# POWER.net
KiCad netlist of a schematic drawn in Altium Designer
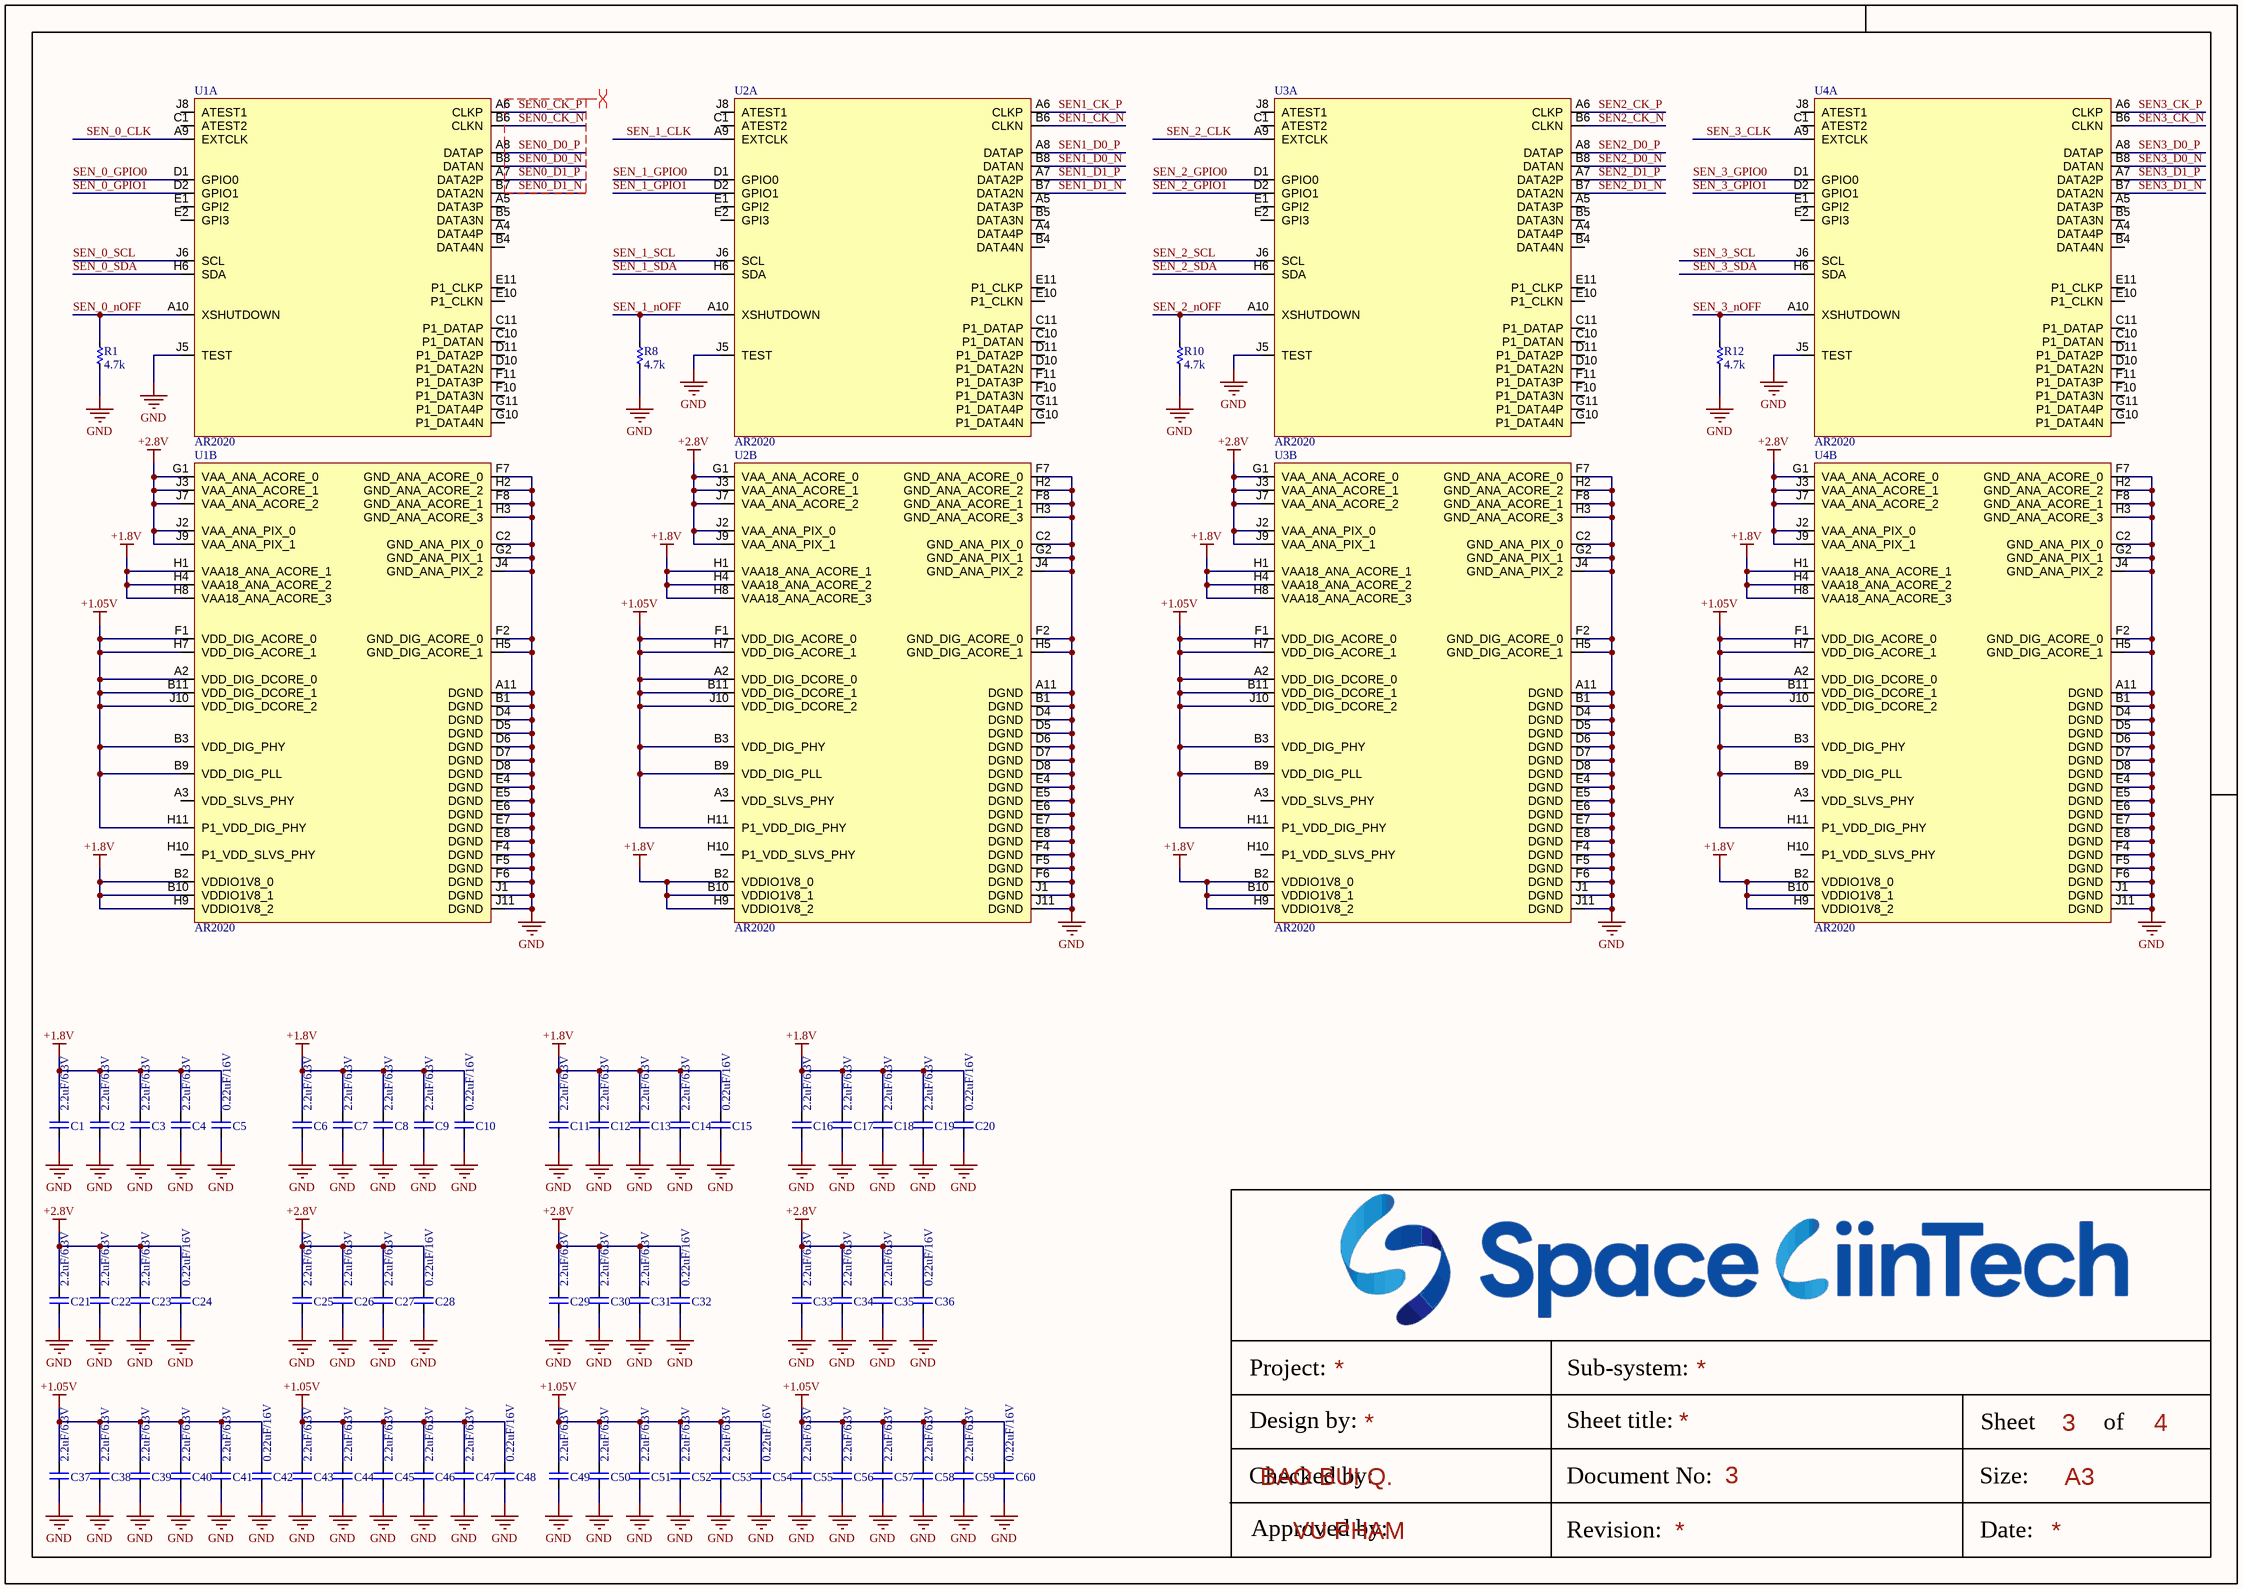
[diagram p0: POWER.SchDoc]

(export (version "E")
  (design (tool "Eeschema 10.0.6"))
  (components
    (comp (ref "C1")
      (value "2.2uF/6.3V")
      (footprint "CAP_C_1005X60")
      (description "CAP_Chip")
      (libsource (lib "LABLIB") (part "CAP_SMD"))
    )
    (comp (ref "C2")
      (value "2.2uF/6.3V")
      (footprint "CAP_C_1005X60")
      (description "CAP_Chip")
      (libsource (lib "LABLIB") (part "CAP_SMD"))
    )
    (comp (ref "C3")
      (value "2.2uF/6.3V")
      (footprint "CAP_C_1005X60")
      (description "CAP_Chip")
      (libsource (lib "LABLIB") (part "CAP_SMD"))
    )
    (comp (ref "C4")
      (value "2.2uF/6.3V")
      (footprint "CAP_C_1005X60")
      (description "CAP_Chip")
      (libsource (lib "LABLIB") (part "CAP_SMD"))
    )
    (comp (ref "C5")
      (value "0.22uF/16V")
      (footprint "CAP_C_1005X60")
      (description "CAP_Chip")
      (libsource (lib "LABLIB") (part "CAP_SMD"))
    )
    (comp (ref "C6")
      (value "2.2uF/6.3V")
      (footprint "CAP_C_1005X60")
      (description "CAP_Chip")
      (libsource (lib "LABLIB") (part "CAP_SMD"))
    )
    (comp (ref "C7")
      (value "2.2uF/6.3V")
      (footprint "CAP_C_1005X60")
      (description "CAP_Chip")
      (libsource (lib "LABLIB") (part "CAP_SMD"))
    )
    (comp (ref "C8")
      (value "2.2uF/6.3V")
      (footprint "CAP_C_1005X60")
      (description "CAP_Chip")
      (libsource (lib "LABLIB") (part "CAP_SMD"))
    )
    (comp (ref "C9")
      (value "2.2uF/6.3V")
      (footprint "CAP_C_1005X60")
      (description "CAP_Chip")
      (libsource (lib "LABLIB") (part "CAP_SMD"))
    )
    (comp (ref "C10")
      (value "0.22uF/16V")
      (footprint "CAP_C_1005X60")
      (description "CAP_Chip")
      (libsource (lib "LABLIB") (part "CAP_SMD"))
    )
    (comp (ref "C11")
      (value "2.2uF/6.3V")
      (footprint "CAP_C_1005X60")
      (description "CAP_Chip")
      (libsource (lib "LABLIB") (part "CAP_SMD"))
    )
    (comp (ref "C12")
      (value "2.2uF/6.3V")
      (footprint "CAP_C_1005X60")
      (description "CAP_Chip")
      (libsource (lib "LABLIB") (part "CAP_SMD"))
    )
    (comp (ref "C13")
      (value "2.2uF/6.3V")
      (footprint "CAP_C_1005X60")
      (description "CAP_Chip")
      (libsource (lib "LABLIB") (part "CAP_SMD"))
    )
    (comp (ref "C14")
      (value "2.2uF/6.3V")
      (footprint "CAP_C_1005X60")
      (description "CAP_Chip")
      (libsource (lib "LABLIB") (part "CAP_SMD"))
    )
    (comp (ref "C15")
      (value "0.22uF/16V")
      (footprint "CAP_C_1005X60")
      (description "CAP_Chip")
      (libsource (lib "LABLIB") (part "CAP_SMD"))
    )
    (comp (ref "C16")
      (value "2.2uF/6.3V")
      (footprint "CAP_C_1005X60")
      (description "CAP_Chip")
      (libsource (lib "LABLIB") (part "CAP_SMD"))
    )
    (comp (ref "C17")
      (value "2.2uF/6.3V")
      (footprint "CAP_C_1005X60")
      (description "CAP_Chip")
      (libsource (lib "LABLIB") (part "CAP_SMD"))
    )
    (comp (ref "C18")
      (value "2.2uF/6.3V")
      (footprint "CAP_C_1005X60")
      (description "CAP_Chip")
      (libsource (lib "LABLIB") (part "CAP_SMD"))
    )
    (comp (ref "C19")
      (value "2.2uF/6.3V")
      (footprint "CAP_C_1005X60")
      (description "CAP_Chip")
      (libsource (lib "LABLIB") (part "CAP_SMD"))
    )
    (comp (ref "C20")
      (value "0.22uF/16V")
      (footprint "CAP_C_1005X60")
      (description "CAP_Chip")
      (libsource (lib "LABLIB") (part "CAP_SMD"))
    )
    (comp (ref "C21")
      (value "2.2uF/6.3V")
      (footprint "CAP_C_1005X60")
      (description "CAP_Chip")
      (libsource (lib "LABLIB") (part "CAP_SMD"))
    )
    (comp (ref "C22")
      (value "2.2uF/6.3V")
      (footprint "CAP_C_1005X60")
      (description "CAP_Chip")
      (libsource (lib "LABLIB") (part "CAP_SMD"))
    )
    (comp (ref "C23")
      (value "2.2uF/6.3V")
      (footprint "CAP_C_1005X60")
      (description "CAP_Chip")
      (libsource (lib "LABLIB") (part "CAP_SMD"))
    )
    (comp (ref "C24")
      (value "0.22uF/16V")
      (footprint "CAP_C_1005X60")
      (description "CAP_Chip")
      (libsource (lib "LABLIB") (part "CAP_SMD"))
    )
    (comp (ref "C25")
      (value "2.2uF/6.3V")
      (footprint "CAP_C_1005X60")
      (description "CAP_Chip")
      (libsource (lib "LABLIB") (part "CAP_SMD"))
    )
    (comp (ref "C26")
      (value "2.2uF/6.3V")
      (footprint "CAP_C_1005X60")
      (description "CAP_Chip")
      (libsource (lib "LABLIB") (part "CAP_SMD"))
    )
    (comp (ref "C27")
      (value "2.2uF/6.3V")
      (footprint "CAP_C_1005X60")
      (description "CAP_Chip")
      (libsource (lib "LABLIB") (part "CAP_SMD"))
    )
    (comp (ref "C28")
      (value "0.22uF/16V")
      (footprint "CAP_C_1005X60")
      (description "CAP_Chip")
      (libsource (lib "LABLIB") (part "CAP_SMD"))
    )
    (comp (ref "C29")
      (value "2.2uF/6.3V")
      (footprint "CAP_C_1005X60")
      (description "CAP_Chip")
      (libsource (lib "LABLIB") (part "CAP_SMD"))
    )
    (comp (ref "C30")
      (value "2.2uF/6.3V")
      (footprint "CAP_C_1005X60")
      (description "CAP_Chip")
      (libsource (lib "LABLIB") (part "CAP_SMD"))
    )
    (comp (ref "C31")
      (value "2.2uF/6.3V")
      (footprint "CAP_C_1005X60")
      (description "CAP_Chip")
      (libsource (lib "LABLIB") (part "CAP_SMD"))
    )
    (comp (ref "C32")
      (value "0.22uF/16V")
      (footprint "CAP_C_1005X60")
      (description "CAP_Chip")
      (libsource (lib "LABLIB") (part "CAP_SMD"))
    )
    (comp (ref "C33")
      (value "2.2uF/6.3V")
      (footprint "CAP_C_1005X60")
      (description "CAP_Chip")
      (libsource (lib "LABLIB") (part "CAP_SMD"))
    )
    (comp (ref "C34")
      (value "2.2uF/6.3V")
      (footprint "CAP_C_1005X60")
      (description "CAP_Chip")
      (libsource (lib "LABLIB") (part "CAP_SMD"))
    )
    (comp (ref "C35")
      (value "2.2uF/6.3V")
      (footprint "CAP_C_1005X60")
      (description "CAP_Chip")
      (libsource (lib "LABLIB") (part "CAP_SMD"))
    )
    (comp (ref "C36")
      (value "0.22uF/16V")
      (footprint "CAP_C_1005X60")
      (description "CAP_Chip")
      (libsource (lib "LABLIB") (part "CAP_SMD"))
    )
    (comp (ref "C37")
      (value "2.2uF/6.3V")
      (footprint "CAP_C_1005X60")
      (description "CAP_Chip")
      (libsource (lib "LABLIB") (part "CAP_SMD"))
    )
    (comp (ref "C38")
      (value "2.2uF/6.3V")
      (footprint "CAP_C_1005X60")
      (description "CAP_Chip")
      (libsource (lib "LABLIB") (part "CAP_SMD"))
    )
    (comp (ref "C39")
      (value "2.2uF/6.3V")
      (footprint "CAP_C_1005X60")
      (description "CAP_Chip")
      (libsource (lib "LABLIB") (part "CAP_SMD"))
    )
    (comp (ref "C40")
      (value "2.2uF/6.3V")
      (footprint "CAP_C_1005X60")
      (description "CAP_Chip")
      (libsource (lib "LABLIB") (part "CAP_SMD"))
    )
    (comp (ref "C41")
      (value "2.2uF/6.3V")
      (footprint "CAP_C_1005X60")
      (description "CAP_Chip")
      (libsource (lib "LABLIB") (part "CAP_SMD"))
    )
    (comp (ref "C42")
      (value "0.22uF/16V")
      (footprint "CAP_C_1005X60")
      (description "CAP_Chip")
      (libsource (lib "LABLIB") (part "CAP_SMD"))
    )
    (comp (ref "C43")
      (value "2.2uF/6.3V")
      (footprint "CAP_C_1005X60")
      (description "CAP_Chip")
      (libsource (lib "LABLIB") (part "CAP_SMD"))
    )
    (comp (ref "C44")
      (value "2.2uF/6.3V")
      (footprint "CAP_C_1005X60")
      (description "CAP_Chip")
      (libsource (lib "LABLIB") (part "CAP_SMD"))
    )
    (comp (ref "C45")
      (value "2.2uF/6.3V")
      (footprint "CAP_C_1005X60")
      (description "CAP_Chip")
      (libsource (lib "LABLIB") (part "CAP_SMD"))
    )
    (comp (ref "C46")
      (value "2.2uF/6.3V")
      (footprint "CAP_C_1005X60")
      (description "CAP_Chip")
      (libsource (lib "LABLIB") (part "CAP_SMD"))
    )
    (comp (ref "C47")
      (value "2.2uF/6.3V")
      (footprint "CAP_C_1005X60")
      (description "CAP_Chip")
      (libsource (lib "LABLIB") (part "CAP_SMD"))
    )
    (comp (ref "C48")
      (value "0.22uF/16V")
      (footprint "CAP_C_1005X60")
      (description "CAP_Chip")
      (libsource (lib "LABLIB") (part "CAP_SMD"))
    )
    (comp (ref "C49")
      (value "2.2uF/6.3V")
      (footprint "CAP_C_1005X60")
      (description "CAP_Chip")
      (libsource (lib "LABLIB") (part "CAP_SMD"))
    )
    (comp (ref "C50")
      (value "2.2uF/6.3V")
      (footprint "CAP_C_1005X60")
      (description "CAP_Chip")
      (libsource (lib "LABLIB") (part "CAP_SMD"))
    )
    (comp (ref "C51")
      (value "2.2uF/6.3V")
      (footprint "CAP_C_1005X60")
      (description "CAP_Chip")
      (libsource (lib "LABLIB") (part "CAP_SMD"))
    )
    (comp (ref "C52")
      (value "2.2uF/6.3V")
      (footprint "CAP_C_1005X60")
      (description "CAP_Chip")
      (libsource (lib "LABLIB") (part "CAP_SMD"))
    )
    (comp (ref "C53")
      (value "2.2uF/6.3V")
      (footprint "CAP_C_1005X60")
      (description "CAP_Chip")
      (libsource (lib "LABLIB") (part "CAP_SMD"))
    )
    (comp (ref "C54")
      (value "0.22uF/16V")
      (footprint "CAP_C_1005X60")
      (description "CAP_Chip")
      (libsource (lib "LABLIB") (part "CAP_SMD"))
    )
    (comp (ref "C55")
      (value "2.2uF/6.3V")
      (footprint "CAP_C_1005X60")
      (description "CAP_Chip")
      (libsource (lib "LABLIB") (part "CAP_SMD"))
    )
    (comp (ref "C56")
      (value "2.2uF/6.3V")
      (footprint "CAP_C_1005X60")
      (description "CAP_Chip")
      (libsource (lib "LABLIB") (part "CAP_SMD"))
    )
    (comp (ref "C57")
      (value "2.2uF/6.3V")
      (footprint "CAP_C_1005X60")
      (description "CAP_Chip")
      (libsource (lib "LABLIB") (part "CAP_SMD"))
    )
    (comp (ref "C58")
      (value "2.2uF/6.3V")
      (footprint "CAP_C_1005X60")
      (description "CAP_Chip")
      (libsource (lib "LABLIB") (part "CAP_SMD"))
    )
    (comp (ref "C59")
      (value "2.2uF/6.3V")
      (footprint "CAP_C_1005X60")
      (description "CAP_Chip")
      (libsource (lib "LABLIB") (part "CAP_SMD"))
    )
    (comp (ref "C60")
      (value "0.22uF/16V")
      (footprint "CAP_C_1005X60")
      (description "CAP_Chip")
      (libsource (lib "LABLIB") (part "CAP_SMD"))
    )
    (comp (ref "R1")
      (value "4.7k")
      (footprint "RES_C_1005X40")
      (description "RES-Chip")
      (fields
        (field (name "MANUFACTURER") "Generic Components")
        (field (name "PUBLISHER") "Altium Hobart Technology Centre")
      )
      (libsource (lib "LABLIB") (part "RES-SMD"))
    )
    (comp (ref "R8")
      (value "4.7k")
      (footprint "RES_C_1005X40")
      (description "RES-Chip")
      (fields
        (field (name "MANUFACTURER") "Generic Components")
        (field (name "PUBLISHER") "Altium Hobart Technology Centre")
      )
      (libsource (lib "LABLIB") (part "RES-SMD"))
    )
    (comp (ref "R10")
      (value "4.7k")
      (footprint "RES_C_1005X40")
      (description "RES-Chip")
      (fields
        (field (name "MANUFACTURER") "Generic Components")
        (field (name "PUBLISHER") "Altium Hobart Technology Centre")
      )
      (libsource (lib "LABLIB") (part "RES-SMD"))
    )
    (comp (ref "R12")
      (value "4.7k")
      (footprint "RES_C_1005X40")
      (description "RES-Chip")
      (fields
        (field (name "MANUFACTURER") "Generic Components")
        (field (name "PUBLISHER") "Altium Hobart Technology Centre")
      )
      (libsource (lib "LABLIB") (part "RES-SMD"))
    )
    (comp (ref "U1")
      (value "AR2020")
      (footprint "BGA78C100P11X9_1300X1050X210")
      (libsource (lib "CAMERA_SchLib") (part "AR2020"))
    )
    (comp (ref "U2")
      (value "AR2020")
      (footprint "BGA78C100P11X9_1300X1050X210")
      (libsource (lib "CAMERA_SchLib") (part "AR2020"))
    )
    (comp (ref "U3")
      (value "AR2020")
      (footprint "BGA78C100P11X9_1300X1050X210")
      (libsource (lib "CAMERA_SchLib") (part "AR2020"))
    )
    (comp (ref "U4")
      (value "AR2020")
      (footprint "BGA78C100P11X9_1300X1050X210")
      (libsource (lib "CAMERA_SchLib") (part "AR2020"))
    )
  )
  (nets
    (net (code "1") (name "+1.05V") (class "Default")
      (node (ref "C37") (pin "2") (pinfunction "2_2") (pintype "passive"))
      (node (ref "C38") (pin "2") (pinfunction "2_2") (pintype "passive"))
      (node (ref "C39") (pin "2") (pinfunction "2_2") (pintype "passive"))
      (node (ref "C40") (pin "2") (pinfunction "2_2") (pintype "passive"))
      (node (ref "C41") (pin "2") (pinfunction "2_2") (pintype "passive"))
      (node (ref "C42") (pin "2") (pinfunction "2_2") (pintype "passive"))
      (node (ref "C43") (pin "2") (pinfunction "2_2") (pintype "passive"))
      (node (ref "C44") (pin "2") (pinfunction "2_2") (pintype "passive"))
      (node (ref "C45") (pin "2") (pinfunction "2_2") (pintype "passive"))
      (node (ref "C46") (pin "2") (pinfunction "2_2") (pintype "passive"))
      (node (ref "C47") (pin "2") (pinfunction "2_2") (pintype "passive"))
      (node (ref "C48") (pin "2") (pinfunction "2_2") (pintype "passive"))
      (node (ref "C49") (pin "2") (pinfunction "2_2") (pintype "passive"))
      (node (ref "C50") (pin "2") (pinfunction "2_2") (pintype "passive"))
      (node (ref "C51") (pin "2") (pinfunction "2_2") (pintype "passive"))
      (node (ref "C52") (pin "2") (pinfunction "2_2") (pintype "passive"))
      (node (ref "C53") (pin "2") (pinfunction "2_2") (pintype "passive"))
      (node (ref "C54") (pin "2") (pinfunction "2_2") (pintype "passive"))
      (node (ref "C55") (pin "2") (pinfunction "2_2") (pintype "passive"))
      (node (ref "C56") (pin "2") (pinfunction "2_2") (pintype "passive"))
      (node (ref "C57") (pin "2") (pinfunction "2_2") (pintype "passive"))
      (node (ref "C58") (pin "2") (pinfunction "2_2") (pintype "passive"))
      (node (ref "C59") (pin "2") (pinfunction "2_2") (pintype "passive"))
      (node (ref "C60") (pin "2") (pinfunction "2_2") (pintype "passive"))
      (node (ref "U1") (pin "A2") (pinfunction "VDD_DIG_DCORE_0_A2") (pintype "passive"))
      (node (ref "U1") (pin "B11") (pinfunction "VDD_DIG_DCORE_1_B11") (pintype "passive"))
      (node (ref "U1") (pin "B3") (pinfunction "VDD_DIG_PHY_B3") (pintype "passive"))
      (node (ref "U1") (pin "B9") (pinfunction "VDD_DIG_PLL_B9") (pintype "passive"))
      (node (ref "U1") (pin "F1") (pinfunction "VDD_DIG_ACORE_0_F1") (pintype "passive"))
      (node (ref "U1") (pin "H11") (pinfunction "P1_VDD_DIG_PHY_H11") (pintype "passive"))
      (node (ref "U1") (pin "H7") (pinfunction "VDD_DIG_ACORE_1_H7") (pintype "passive"))
      (node (ref "U1") (pin "J10") (pinfunction "VDD_DIG_DCORE_2_J10") (pintype "passive"))
      (node (ref "U2") (pin "A2") (pinfunction "VDD_DIG_DCORE_0_A2") (pintype "passive"))
      (node (ref "U2") (pin "B11") (pinfunction "VDD_DIG_DCORE_1_B11") (pintype "passive"))
      (node (ref "U2") (pin "B3") (pinfunction "VDD_DIG_PHY_B3") (pintype "passive"))
      (node (ref "U2") (pin "B9") (pinfunction "VDD_DIG_PLL_B9") (pintype "passive"))
      (node (ref "U2") (pin "F1") (pinfunction "VDD_DIG_ACORE_0_F1") (pintype "passive"))
      (node (ref "U2") (pin "H11") (pinfunction "P1_VDD_DIG_PHY_H11") (pintype "passive"))
      (node (ref "U2") (pin "H7") (pinfunction "VDD_DIG_ACORE_1_H7") (pintype "passive"))
      (node (ref "U2") (pin "J10") (pinfunction "VDD_DIG_DCORE_2_J10") (pintype "passive"))
      (node (ref "U3") (pin "A2") (pinfunction "VDD_DIG_DCORE_0_A2") (pintype "passive"))
      (node (ref "U3") (pin "B11") (pinfunction "VDD_DIG_DCORE_1_B11") (pintype "passive"))
      (node (ref "U3") (pin "B3") (pinfunction "VDD_DIG_PHY_B3") (pintype "passive"))
      (node (ref "U3") (pin "B9") (pinfunction "VDD_DIG_PLL_B9") (pintype "passive"))
      (node (ref "U3") (pin "F1") (pinfunction "VDD_DIG_ACORE_0_F1") (pintype "passive"))
      (node (ref "U3") (pin "H11") (pinfunction "P1_VDD_DIG_PHY_H11") (pintype "passive"))
      (node (ref "U3") (pin "H7") (pinfunction "VDD_DIG_ACORE_1_H7") (pintype "passive"))
      (node (ref "U3") (pin "J10") (pinfunction "VDD_DIG_DCORE_2_J10") (pintype "passive"))
      (node (ref "U4") (pin "A2") (pinfunction "VDD_DIG_DCORE_0_A2") (pintype "passive"))
      (node (ref "U4") (pin "B11") (pinfunction "VDD_DIG_DCORE_1_B11") (pintype "passive"))
      (node (ref "U4") (pin "B3") (pinfunction "VDD_DIG_PHY_B3") (pintype "passive"))
      (node (ref "U4") (pin "B9") (pinfunction "VDD_DIG_PLL_B9") (pintype "passive"))
      (node (ref "U4") (pin "F1") (pinfunction "VDD_DIG_ACORE_0_F1") (pintype "passive"))
      (node (ref "U4") (pin "H11") (pinfunction "P1_VDD_DIG_PHY_H11") (pintype "passive"))
      (node (ref "U4") (pin "H7") (pinfunction "VDD_DIG_ACORE_1_H7") (pintype "passive"))
      (node (ref "U4") (pin "J10") (pinfunction "VDD_DIG_DCORE_2_J10") (pintype "passive"))
    )
    (net (code "2") (name "+1.8V") (class "Default")
      (node (ref "C1") (pin "2") (pinfunction "2_2") (pintype "passive"))
      (node (ref "C10") (pin "2") (pinfunction "2_2") (pintype "passive"))
      (node (ref "C11") (pin "2") (pinfunction "2_2") (pintype "passive"))
      (node (ref "C12") (pin "2") (pinfunction "2_2") (pintype "passive"))
      (node (ref "C13") (pin "2") (pinfunction "2_2") (pintype "passive"))
      (node (ref "C14") (pin "2") (pinfunction "2_2") (pintype "passive"))
      (node (ref "C15") (pin "2") (pinfunction "2_2") (pintype "passive"))
      (node (ref "C16") (pin "2") (pinfunction "2_2") (pintype "passive"))
      (node (ref "C17") (pin "2") (pinfunction "2_2") (pintype "passive"))
      (node (ref "C18") (pin "2") (pinfunction "2_2") (pintype "passive"))
      (node (ref "C19") (pin "2") (pinfunction "2_2") (pintype "passive"))
      (node (ref "C2") (pin "2") (pinfunction "2_2") (pintype "passive"))
      (node (ref "C20") (pin "2") (pinfunction "2_2") (pintype "passive"))
      (node (ref "C3") (pin "2") (pinfunction "2_2") (pintype "passive"))
      (node (ref "C4") (pin "2") (pinfunction "2_2") (pintype "passive"))
      (node (ref "C5") (pin "2") (pinfunction "2_2") (pintype "passive"))
      (node (ref "C6") (pin "2") (pinfunction "2_2") (pintype "passive"))
      (node (ref "C7") (pin "2") (pinfunction "2_2") (pintype "passive"))
      (node (ref "C8") (pin "2") (pinfunction "2_2") (pintype "passive"))
      (node (ref "C9") (pin "2") (pinfunction "2_2") (pintype "passive"))
      (node (ref "U1") (pin "B10") (pinfunction "VDDIO1V8_1_B10") (pintype "passive"))
      (node (ref "U1") (pin "B2") (pinfunction "VDDIO1V8_0_B2") (pintype "passive"))
      (node (ref "U1") (pin "H1") (pinfunction "VAA18_ANA_ACORE_1_H1") (pintype "passive"))
      (node (ref "U1") (pin "H4") (pinfunction "VAA18_ANA_ACORE_2_H4") (pintype "passive"))
      (node (ref "U1") (pin "H8") (pinfunction "VAA18_ANA_ACORE_3_H8") (pintype "passive"))
      (node (ref "U1") (pin "H9") (pinfunction "VDDIO1V8_2_H9") (pintype "passive"))
      (node (ref "U2") (pin "B10") (pinfunction "VDDIO1V8_1_B10") (pintype "passive"))
      (node (ref "U2") (pin "B2") (pinfunction "VDDIO1V8_0_B2") (pintype "passive"))
      (node (ref "U2") (pin "H1") (pinfunction "VAA18_ANA_ACORE_1_H1") (pintype "passive"))
      (node (ref "U2") (pin "H4") (pinfunction "VAA18_ANA_ACORE_2_H4") (pintype "passive"))
      (node (ref "U2") (pin "H8") (pinfunction "VAA18_ANA_ACORE_3_H8") (pintype "passive"))
      (node (ref "U2") (pin "H9") (pinfunction "VDDIO1V8_2_H9") (pintype "passive"))
      (node (ref "U3") (pin "B10") (pinfunction "VDDIO1V8_1_B10") (pintype "passive"))
      (node (ref "U3") (pin "B2") (pinfunction "VDDIO1V8_0_B2") (pintype "passive"))
      (node (ref "U3") (pin "H1") (pinfunction "VAA18_ANA_ACORE_1_H1") (pintype "passive"))
      (node (ref "U3") (pin "H4") (pinfunction "VAA18_ANA_ACORE_2_H4") (pintype "passive"))
      (node (ref "U3") (pin "H8") (pinfunction "VAA18_ANA_ACORE_3_H8") (pintype "passive"))
      (node (ref "U3") (pin "H9") (pinfunction "VDDIO1V8_2_H9") (pintype "passive"))
      (node (ref "U4") (pin "B10") (pinfunction "VDDIO1V8_1_B10") (pintype "passive"))
      (node (ref "U4") (pin "B2") (pinfunction "VDDIO1V8_0_B2") (pintype "passive"))
      (node (ref "U4") (pin "H1") (pinfunction "VAA18_ANA_ACORE_1_H1") (pintype "passive"))
      (node (ref "U4") (pin "H4") (pinfunction "VAA18_ANA_ACORE_2_H4") (pintype "passive"))
      (node (ref "U4") (pin "H8") (pinfunction "VAA18_ANA_ACORE_3_H8") (pintype "passive"))
      (node (ref "U4") (pin "H9") (pinfunction "VDDIO1V8_2_H9") (pintype "passive"))
    )
    (net (code "3") (name "+2.8V") (class "Default")
      (node (ref "C21") (pin "2") (pinfunction "2_2") (pintype "passive"))
      (node (ref "C22") (pin "2") (pinfunction "2_2") (pintype "passive"))
      (node (ref "C23") (pin "2") (pinfunction "2_2") (pintype "passive"))
      (node (ref "C24") (pin "2") (pinfunction "2_2") (pintype "passive"))
      (node (ref "C25") (pin "2") (pinfunction "2_2") (pintype "passive"))
      (node (ref "C26") (pin "2") (pinfunction "2_2") (pintype "passive"))
      (node (ref "C27") (pin "2") (pinfunction "2_2") (pintype "passive"))
      (node (ref "C28") (pin "2") (pinfunction "2_2") (pintype "passive"))
      (node (ref "C29") (pin "2") (pinfunction "2_2") (pintype "passive"))
      (node (ref "C30") (pin "2") (pinfunction "2_2") (pintype "passive"))
      (node (ref "C31") (pin "2") (pinfunction "2_2") (pintype "passive"))
      (node (ref "C32") (pin "2") (pinfunction "2_2") (pintype "passive"))
      (node (ref "C33") (pin "2") (pinfunction "2_2") (pintype "passive"))
      (node (ref "C34") (pin "2") (pinfunction "2_2") (pintype "passive"))
      (node (ref "C35") (pin "2") (pinfunction "2_2") (pintype "passive"))
      (node (ref "C36") (pin "2") (pinfunction "2_2") (pintype "passive"))
      (node (ref "U1") (pin "G1") (pinfunction "VAA_ANA_ACORE_0_G1") (pintype "passive"))
      (node (ref "U1") (pin "J2") (pinfunction "VAA_ANA_PIX_0_J2") (pintype "passive"))
      (node (ref "U1") (pin "J3") (pinfunction "VAA_ANA_ACORE_1_J3") (pintype "passive"))
      (node (ref "U1") (pin "J7") (pinfunction "VAA_ANA_ACORE_2_J7") (pintype "passive"))
      (node (ref "U1") (pin "J9") (pinfunction "VAA_ANA_PIX_1_J9") (pintype "passive"))
      (node (ref "U2") (pin "G1") (pinfunction "VAA_ANA_ACORE_0_G1") (pintype "passive"))
      (node (ref "U2") (pin "J2") (pinfunction "VAA_ANA_PIX_0_J2") (pintype "passive"))
      (node (ref "U2") (pin "J3") (pinfunction "VAA_ANA_ACORE_1_J3") (pintype "passive"))
      (node (ref "U2") (pin "J7") (pinfunction "VAA_ANA_ACORE_2_J7") (pintype "passive"))
      (node (ref "U2") (pin "J9") (pinfunction "VAA_ANA_PIX_1_J9") (pintype "passive"))
      (node (ref "U3") (pin "G1") (pinfunction "VAA_ANA_ACORE_0_G1") (pintype "passive"))
      (node (ref "U3") (pin "J2") (pinfunction "VAA_ANA_PIX_0_J2") (pintype "passive"))
      (node (ref "U3") (pin "J3") (pinfunction "VAA_ANA_ACORE_1_J3") (pintype "passive"))
      (node (ref "U3") (pin "J7") (pinfunction "VAA_ANA_ACORE_2_J7") (pintype "passive"))
      (node (ref "U3") (pin "J9") (pinfunction "VAA_ANA_PIX_1_J9") (pintype "passive"))
      (node (ref "U4") (pin "G1") (pinfunction "VAA_ANA_ACORE_0_G1") (pintype "passive"))
      (node (ref "U4") (pin "J2") (pinfunction "VAA_ANA_PIX_0_J2") (pintype "passive"))
      (node (ref "U4") (pin "J3") (pinfunction "VAA_ANA_ACORE_1_J3") (pintype "passive"))
      (node (ref "U4") (pin "J7") (pinfunction "VAA_ANA_ACORE_2_J7") (pintype "passive"))
      (node (ref "U4") (pin "J9") (pinfunction "VAA_ANA_PIX_1_J9") (pintype "passive"))
    )
    (net (code "4") (name "/SEN0_CK_N") (class "Default")
      (node (ref "U1") (pin "B6") (pinfunction "CLKN_B6") (pintype "passive"))
    )
    (net (code "5") (name "/SEN0_CK_P") (class "Default")
      (node (ref "U1") (pin "A6") (pinfunction "CLKP_A6") (pintype "passive"))
    )
    (net (code "6") (name "/SEN0_D0_N") (class "Default")
      (node (ref "U1") (pin "B8") (pinfunction "DATAN_B8") (pintype "passive"))
    )
    (net (code "7") (name "/SEN0_D0_P") (class "Default")
      (node (ref "U1") (pin "A8") (pinfunction "DATAP_A8") (pintype "passive"))
    )
    (net (code "8") (name "/SEN0_D1_N") (class "Default")
      (node (ref "U1") (pin "B7") (pinfunction "DATA2N_B7") (pintype "passive"))
    )
    (net (code "9") (name "/SEN0_D1_P") (class "Default")
      (node (ref "U1") (pin "A7") (pinfunction "DATA2P_A7") (pintype "passive"))
    )
    (net (code "10") (name "/SEN1_CK_N") (class "Default")
      (node (ref "U2") (pin "B6") (pinfunction "CLKN_B6") (pintype "passive"))
    )
    (net (code "11") (name "/SEN1_CK_P") (class "Default")
      (node (ref "U2") (pin "A6") (pinfunction "CLKP_A6") (pintype "passive"))
    )
    (net (code "12") (name "/SEN1_D0_N") (class "Default")
      (node (ref "U2") (pin "B8") (pinfunction "DATAN_B8") (pintype "passive"))
    )
    (net (code "13") (name "/SEN1_D0_P") (class "Default")
      (node (ref "U2") (pin "A8") (pinfunction "DATAP_A8") (pintype "passive"))
    )
    (net (code "14") (name "/SEN1_D1_N") (class "Default")
      (node (ref "U2") (pin "B7") (pinfunction "DATA2N_B7") (pintype "passive"))
    )
    (net (code "15") (name "/SEN1_D1_P") (class "Default")
      (node (ref "U2") (pin "A7") (pinfunction "DATA2P_A7") (pintype "passive"))
    )
    (net (code "16") (name "/SEN2_CK_N") (class "Default")
      (node (ref "U3") (pin "B6") (pinfunction "CLKN_B6") (pintype "passive"))
    )
    (net (code "17") (name "/SEN2_CK_P") (class "Default")
      (node (ref "U3") (pin "A6") (pinfunction "CLKP_A6") (pintype "passive"))
    )
    (net (code "18") (name "/SEN2_D0_N") (class "Default")
      (node (ref "U3") (pin "B8") (pinfunction "DATAN_B8") (pintype "passive"))
    )
    (net (code "19") (name "/SEN2_D0_P") (class "Default")
      (node (ref "U3") (pin "A8") (pinfunction "DATAP_A8") (pintype "passive"))
    )
    (net (code "20") (name "/SEN2_D1_N") (class "Default")
      (node (ref "U3") (pin "B7") (pinfunction "DATA2N_B7") (pintype "passive"))
    )
    (net (code "21") (name "/SEN2_D1_P") (class "Default")
      (node (ref "U3") (pin "A7") (pinfunction "DATA2P_A7") (pintype "passive"))
    )
    (net (code "22") (name "/SEN3_CK_N") (class "Default")
      (node (ref "U4") (pin "B6") (pinfunction "CLKN_B6") (pintype "passive"))
    )
    (net (code "23") (name "/SEN3_CK_P") (class "Default")
      (node (ref "U4") (pin "A6") (pinfunction "CLKP_A6") (pintype "passive"))
    )
    (net (code "24") (name "/SEN3_D0_N") (class "Default")
      (node (ref "U4") (pin "B8") (pinfunction "DATAN_B8") (pintype "passive"))
    )
    (net (code "25") (name "/SEN3_D0_P") (class "Default")
      (node (ref "U4") (pin "A8") (pinfunction "DATAP_A8") (pintype "passive"))
    )
    (net (code "26") (name "/SEN3_D1_N") (class "Default")
      (node (ref "U4") (pin "B7") (pinfunction "DATA2N_B7") (pintype "passive"))
    )
    (net (code "27") (name "/SEN3_D1_P") (class "Default")
      (node (ref "U4") (pin "A7") (pinfunction "DATA2P_A7") (pintype "passive"))
    )
    (net (code "28") (name "/SEN_0_CLK") (class "Default")
      (node (ref "U1") (pin "A9") (pinfunction "EXTCLK_A9") (pintype "passive"))
    )
    (net (code "29") (name "/SEN_0_GPIO0") (class "Default")
      (node (ref "U1") (pin "D1") (pinfunction "GPIO0_D1") (pintype "passive"))
    )
    (net (code "30") (name "/SEN_0_GPIO1") (class "Default")
      (node (ref "U1") (pin "D2") (pinfunction "GPIO1_D2") (pintype "passive"))
    )
    (net (code "31") (name "/SEN_0_SCL") (class "Default")
      (node (ref "U1") (pin "J6") (pinfunction "SCL_J6") (pintype "passive"))
    )
    (net (code "32") (name "/SEN_0_SDA") (class "Default")
      (node (ref "U1") (pin "H6") (pinfunction "SDA_H6") (pintype "passive"))
    )
    (net (code "33") (name "/SEN_0_nOFF") (class "Default")
      (node (ref "R1") (pin "1") (pinfunction "1_1") (pintype "passive"))
      (node (ref "U1") (pin "A10") (pinfunction "XSHUTDOWN_A10") (pintype "passive"))
    )
    (net (code "34") (name "/SEN_1_CLK") (class "Default")
      (node (ref "U2") (pin "A9") (pinfunction "EXTCLK_A9") (pintype "passive"))
    )
    (net (code "35") (name "/SEN_1_GPIO0") (class "Default")
      (node (ref "U2") (pin "D1") (pinfunction "GPIO0_D1") (pintype "passive"))
    )
    (net (code "36") (name "/SEN_1_GPIO1") (class "Default")
      (node (ref "U2") (pin "D2") (pinfunction "GPIO1_D2") (pintype "passive"))
    )
    (net (code "37") (name "/SEN_1_SCL") (class "Default")
      (node (ref "U2") (pin "J6") (pinfunction "SCL_J6") (pintype "passive"))
    )
    (net (code "38") (name "/SEN_1_SDA") (class "Default")
      (node (ref "U2") (pin "H6") (pinfunction "SDA_H6") (pintype "passive"))
    )
    (net (code "39") (name "/SEN_1_nOFF") (class "Default")
      (node (ref "R8") (pin "1") (pinfunction "1_1") (pintype "passive"))
      (node (ref "U2") (pin "A10") (pinfunction "XSHUTDOWN_A10") (pintype "passive"))
    )
    (net (code "40") (name "/SEN_2_CLK") (class "Default")
      (node (ref "U3") (pin "A9") (pinfunction "EXTCLK_A9") (pintype "passive"))
    )
    (net (code "41") (name "/SEN_2_GPIO0") (class "Default")
      (node (ref "U3") (pin "D1") (pinfunction "GPIO0_D1") (pintype "passive"))
    )
    (net (code "42") (name "/SEN_2_GPIO1") (class "Default")
      (node (ref "U3") (pin "D2") (pinfunction "GPIO1_D2") (pintype "passive"))
    )
    (net (code "43") (name "/SEN_2_SCL") (class "Default")
      (node (ref "U3") (pin "J6") (pinfunction "SCL_J6") (pintype "passive"))
    )
    (net (code "44") (name "/SEN_2_SDA") (class "Default")
      (node (ref "U3") (pin "H6") (pinfunction "SDA_H6") (pintype "passive"))
    )
    (net (code "45") (name "/SEN_2_nOFF") (class "Default")
      (node (ref "R10") (pin "1") (pinfunction "1_1") (pintype "passive"))
      (node (ref "U3") (pin "A10") (pinfunction "XSHUTDOWN_A10") (pintype "passive"))
    )
    (net (code "46") (name "/SEN_3_CLK") (class "Default")
      (node (ref "U4") (pin "A9") (pinfunction "EXTCLK_A9") (pintype "passive"))
    )
    (net (code "47") (name "/SEN_3_GPIO0") (class "Default")
      (node (ref "U4") (pin "D1") (pinfunction "GPIO0_D1") (pintype "passive"))
    )
    (net (code "48") (name "/SEN_3_GPIO1") (class "Default")
      (node (ref "U4") (pin "D2") (pinfunction "GPIO1_D2") (pintype "passive"))
    )
    (net (code "49") (name "/SEN_3_SCL") (class "Default")
      (node (ref "U4") (pin "J6") (pinfunction "SCL_J6") (pintype "passive"))
    )
    (net (code "50") (name "/SEN_3_SDA") (class "Default")
      (node (ref "U4") (pin "H6") (pinfunction "SDA_H6") (pintype "passive"))
    )
    (net (code "51") (name "/SEN_3_nOFF") (class "Default")
      (node (ref "R12") (pin "1") (pinfunction "1_1") (pintype "passive"))
      (node (ref "U4") (pin "A10") (pinfunction "XSHUTDOWN_A10") (pintype "passive"))
    )
    (net (code "52") (name "GND") (class "Default")
      (node (ref "C1") (pin "1") (pinfunction "1_1") (pintype "passive"))
      (node (ref "C10") (pin "1") (pinfunction "1_1") (pintype "passive"))
      (node (ref "C11") (pin "1") (pinfunction "1_1") (pintype "passive"))
      (node (ref "C12") (pin "1") (pinfunction "1_1") (pintype "passive"))
      (node (ref "C13") (pin "1") (pinfunction "1_1") (pintype "passive"))
      (node (ref "C14") (pin "1") (pinfunction "1_1") (pintype "passive"))
      (node (ref "C15") (pin "1") (pinfunction "1_1") (pintype "passive"))
      (node (ref "C16") (pin "1") (pinfunction "1_1") (pintype "passive"))
      (node (ref "C17") (pin "1") (pinfunction "1_1") (pintype "passive"))
      (node (ref "C18") (pin "1") (pinfunction "1_1") (pintype "passive"))
      (node (ref "C19") (pin "1") (pinfunction "1_1") (pintype "passive"))
      (node (ref "C2") (pin "1") (pinfunction "1_1") (pintype "passive"))
      (node (ref "C20") (pin "1") (pinfunction "1_1") (pintype "passive"))
      (node (ref "C21") (pin "1") (pinfunction "1_1") (pintype "passive"))
      (node (ref "C22") (pin "1") (pinfunction "1_1") (pintype "passive"))
      (node (ref "C23") (pin "1") (pinfunction "1_1") (pintype "passive"))
      (node (ref "C24") (pin "1") (pinfunction "1_1") (pintype "passive"))
      (node (ref "C25") (pin "1") (pinfunction "1_1") (pintype "passive"))
      (node (ref "C26") (pin "1") (pinfunction "1_1") (pintype "passive"))
      (node (ref "C27") (pin "1") (pinfunction "1_1") (pintype "passive"))
      (node (ref "C28") (pin "1") (pinfunction "1_1") (pintype "passive"))
      (node (ref "C29") (pin "1") (pinfunction "1_1") (pintype "passive"))
      (node (ref "C3") (pin "1") (pinfunction "1_1") (pintype "passive"))
      (node (ref "C30") (pin "1") (pinfunction "1_1") (pintype "passive"))
      (node (ref "C31") (pin "1") (pinfunction "1_1") (pintype "passive"))
      (node (ref "C32") (pin "1") (pinfunction "1_1") (pintype "passive"))
      (node (ref "C33") (pin "1") (pinfunction "1_1") (pintype "passive"))
      (node (ref "C34") (pin "1") (pinfunction "1_1") (pintype "passive"))
      (node (ref "C35") (pin "1") (pinfunction "1_1") (pintype "passive"))
      (node (ref "C36") (pin "1") (pinfunction "1_1") (pintype "passive"))
      (node (ref "C37") (pin "1") (pinfunction "1_1") (pintype "passive"))
      (node (ref "C38") (pin "1") (pinfunction "1_1") (pintype "passive"))
      (node (ref "C39") (pin "1") (pinfunction "1_1") (pintype "passive"))
      (node (ref "C4") (pin "1") (pinfunction "1_1") (pintype "passive"))
      (node (ref "C40") (pin "1") (pinfunction "1_1") (pintype "passive"))
      (node (ref "C41") (pin "1") (pinfunction "1_1") (pintype "passive"))
      (node (ref "C42") (pin "1") (pinfunction "1_1") (pintype "passive"))
      (node (ref "C43") (pin "1") (pinfunction "1_1") (pintype "passive"))
      (node (ref "C44") (pin "1") (pinfunction "1_1") (pintype "passive"))
      (node (ref "C45") (pin "1") (pinfunction "1_1") (pintype "passive"))
      (node (ref "C46") (pin "1") (pinfunction "1_1") (pintype "passive"))
      (node (ref "C47") (pin "1") (pinfunction "1_1") (pintype "passive"))
      (node (ref "C48") (pin "1") (pinfunction "1_1") (pintype "passive"))
      (node (ref "C49") (pin "1") (pinfunction "1_1") (pintype "passive"))
      (node (ref "C5") (pin "1") (pinfunction "1_1") (pintype "passive"))
      (node (ref "C50") (pin "1") (pinfunction "1_1") (pintype "passive"))
      (node (ref "C51") (pin "1") (pinfunction "1_1") (pintype "passive"))
      (node (ref "C52") (pin "1") (pinfunction "1_1") (pintype "passive"))
      (node (ref "C53") (pin "1") (pinfunction "1_1") (pintype "passive"))
      (node (ref "C54") (pin "1") (pinfunction "1_1") (pintype "passive"))
      (node (ref "C55") (pin "1") (pinfunction "1_1") (pintype "passive"))
      (node (ref "C56") (pin "1") (pinfunction "1_1") (pintype "passive"))
      (node (ref "C57") (pin "1") (pinfunction "1_1") (pintype "passive"))
      (node (ref "C58") (pin "1") (pinfunction "1_1") (pintype "passive"))
      (node (ref "C59") (pin "1") (pinfunction "1_1") (pintype "passive"))
      (node (ref "C6") (pin "1") (pinfunction "1_1") (pintype "passive"))
      (node (ref "C60") (pin "1") (pinfunction "1_1") (pintype "passive"))
      (node (ref "C7") (pin "1") (pinfunction "1_1") (pintype "passive"))
      (node (ref "C8") (pin "1") (pinfunction "1_1") (pintype "passive"))
      (node (ref "C9") (pin "1") (pinfunction "1_1") (pintype "passive"))
      (node (ref "R1") (pin "2") (pinfunction "2_2") (pintype "passive"))
      (node (ref "R10") (pin "2") (pinfunction "2_2") (pintype "passive"))
      (node (ref "R12") (pin "2") (pinfunction "2_2") (pintype "passive"))
      (node (ref "R8") (pin "2") (pinfunction "2_2") (pintype "passive"))
      (node (ref "U1") (pin "A11") (pinfunction "DGND_A11") (pintype "passive"))
      (node (ref "U1") (pin "B1") (pinfunction "DGND_B1") (pintype "passive"))
      (node (ref "U1") (pin "C2") (pinfunction "GND_ANA_PIX_0_C2") (pintype "passive"))
      (node (ref "U1") (pin "D4") (pinfunction "DGND_D4") (pintype "passive"))
      (node (ref "U1") (pin "D5") (pinfunction "DGND_D5") (pintype "passive"))
      (node (ref "U1") (pin "D6") (pinfunction "DGND_D6") (pintype "passive"))
      (node (ref "U1") (pin "D7") (pinfunction "DGND_D7") (pintype "passive"))
      (node (ref "U1") (pin "D8") (pinfunction "DGND_D8") (pintype "passive"))
      (node (ref "U1") (pin "E4") (pinfunction "DGND_E4") (pintype "passive"))
      (node (ref "U1") (pin "E5") (pinfunction "DGND_E5") (pintype "passive"))
      (node (ref "U1") (pin "E6") (pinfunction "DGND_E6") (pintype "passive"))
      (node (ref "U1") (pin "E7") (pinfunction "DGND_E7") (pintype "passive"))
      (node (ref "U1") (pin "E8") (pinfunction "DGND_E8") (pintype "passive"))
      (node (ref "U1") (pin "F2") (pinfunction "GND_DIG_ACORE_0_F2") (pintype "passive"))
      (node (ref "U1") (pin "F4") (pinfunction "DGND_F4") (pintype "passive"))
      (node (ref "U1") (pin "F5") (pinfunction "DGND_F5") (pintype "passive"))
      (node (ref "U1") (pin "F6") (pinfunction "DGND_F6") (pintype "passive"))
      (node (ref "U1") (pin "F7") (pinfunction "GND_ANA_ACORE_0_F7") (pintype "passive"))
      (node (ref "U1") (pin "F8") (pinfunction "GND_ANA_ACORE_1_F8") (pintype "passive"))
      (node (ref "U1") (pin "G2") (pinfunction "GND_ANA_PIX_1_G2") (pintype "passive"))
      (node (ref "U1") (pin "H2") (pinfunction "GND_ANA_ACORE_2_H2") (pintype "passive"))
      (node (ref "U1") (pin "H3") (pinfunction "GND_ANA_ACORE_3_H3") (pintype "passive"))
      (node (ref "U1") (pin "H5") (pinfunction "GND_DIG_ACORE_1_H5") (pintype "passive"))
      (node (ref "U1") (pin "J1") (pinfunction "DGND_J1") (pintype "passive"))
      (node (ref "U1") (pin "J11") (pinfunction "DGND_J11") (pintype "passive"))
      (node (ref "U1") (pin "J4") (pinfunction "GND_ANA_PIX_2_J4") (pintype "passive"))
      (node (ref "U1") (pin "J5") (pinfunction "TEST_J5") (pintype "passive"))
      (node (ref "U2") (pin "A11") (pinfunction "DGND_A11") (pintype "passive"))
      (node (ref "U2") (pin "B1") (pinfunction "DGND_B1") (pintype "passive"))
      (node (ref "U2") (pin "C2") (pinfunction "GND_ANA_PIX_0_C2") (pintype "passive"))
      (node (ref "U2") (pin "D4") (pinfunction "DGND_D4") (pintype "passive"))
      (node (ref "U2") (pin "D5") (pinfunction "DGND_D5") (pintype "passive"))
      (node (ref "U2") (pin "D6") (pinfunction "DGND_D6") (pintype "passive"))
      (node (ref "U2") (pin "D7") (pinfunction "DGND_D7") (pintype "passive"))
      (node (ref "U2") (pin "D8") (pinfunction "DGND_D8") (pintype "passive"))
      (node (ref "U2") (pin "E4") (pinfunction "DGND_E4") (pintype "passive"))
      (node (ref "U2") (pin "E5") (pinfunction "DGND_E5") (pintype "passive"))
      (node (ref "U2") (pin "E6") (pinfunction "DGND_E6") (pintype "passive"))
      (node (ref "U2") (pin "E7") (pinfunction "DGND_E7") (pintype "passive"))
      (node (ref "U2") (pin "E8") (pinfunction "DGND_E8") (pintype "passive"))
      (node (ref "U2") (pin "F2") (pinfunction "GND_DIG_ACORE_0_F2") (pintype "passive"))
      (node (ref "U2") (pin "F4") (pinfunction "DGND_F4") (pintype "passive"))
      (node (ref "U2") (pin "F5") (pinfunction "DGND_F5") (pintype "passive"))
      (node (ref "U2") (pin "F6") (pinfunction "DGND_F6") (pintype "passive"))
      (node (ref "U2") (pin "F7") (pinfunction "GND_ANA_ACORE_0_F7") (pintype "passive"))
      (node (ref "U2") (pin "F8") (pinfunction "GND_ANA_ACORE_1_F8") (pintype "passive"))
      (node (ref "U2") (pin "G2") (pinfunction "GND_ANA_PIX_1_G2") (pintype "passive"))
      (node (ref "U2") (pin "H2") (pinfunction "GND_ANA_ACORE_2_H2") (pintype "passive"))
      (node (ref "U2") (pin "H3") (pinfunction "GND_ANA_ACORE_3_H3") (pintype "passive"))
      (node (ref "U2") (pin "H5") (pinfunction "GND_DIG_ACORE_1_H5") (pintype "passive"))
      (node (ref "U2") (pin "J1") (pinfunction "DGND_J1") (pintype "passive"))
      (node (ref "U2") (pin "J11") (pinfunction "DGND_J11") (pintype "passive"))
      (node (ref "U2") (pin "J4") (pinfunction "GND_ANA_PIX_2_J4") (pintype "passive"))
      (node (ref "U2") (pin "J5") (pinfunction "TEST_J5") (pintype "passive"))
      (node (ref "U3") (pin "A11") (pinfunction "DGND_A11") (pintype "passive"))
      (node (ref "U3") (pin "B1") (pinfunction "DGND_B1") (pintype "passive"))
      (node (ref "U3") (pin "C2") (pinfunction "GND_ANA_PIX_0_C2") (pintype "passive"))
      (node (ref "U3") (pin "D4") (pinfunction "DGND_D4") (pintype "passive"))
      (node (ref "U3") (pin "D5") (pinfunction "DGND_D5") (pintype "passive"))
      (node (ref "U3") (pin "D6") (pinfunction "DGND_D6") (pintype "passive"))
      (node (ref "U3") (pin "D7") (pinfunction "DGND_D7") (pintype "passive"))
      (node (ref "U3") (pin "D8") (pinfunction "DGND_D8") (pintype "passive"))
      (node (ref "U3") (pin "E4") (pinfunction "DGND_E4") (pintype "passive"))
      (node (ref "U3") (pin "E5") (pinfunction "DGND_E5") (pintype "passive"))
      (node (ref "U3") (pin "E6") (pinfunction "DGND_E6") (pintype "passive"))
      (node (ref "U3") (pin "E7") (pinfunction "DGND_E7") (pintype "passive"))
      (node (ref "U3") (pin "E8") (pinfunction "DGND_E8") (pintype "passive"))
      (node (ref "U3") (pin "F2") (pinfunction "GND_DIG_ACORE_0_F2") (pintype "passive"))
      (node (ref "U3") (pin "F4") (pinfunction "DGND_F4") (pintype "passive"))
      (node (ref "U3") (pin "F5") (pinfunction "DGND_F5") (pintype "passive"))
      (node (ref "U3") (pin "F6") (pinfunction "DGND_F6") (pintype "passive"))
      (node (ref "U3") (pin "F7") (pinfunction "GND_ANA_ACORE_0_F7") (pintype "passive"))
      (node (ref "U3") (pin "F8") (pinfunction "GND_ANA_ACORE_1_F8") (pintype "passive"))
      (node (ref "U3") (pin "G2") (pinfunction "GND_ANA_PIX_1_G2") (pintype "passive"))
      (node (ref "U3") (pin "H2") (pinfunction "GND_ANA_ACORE_2_H2") (pintype "passive"))
      (node (ref "U3") (pin "H3") (pinfunction "GND_ANA_ACORE_3_H3") (pintype "passive"))
      (node (ref "U3") (pin "H5") (pinfunction "GND_DIG_ACORE_1_H5") (pintype "passive"))
      (node (ref "U3") (pin "J1") (pinfunction "DGND_J1") (pintype "passive"))
      (node (ref "U3") (pin "J11") (pinfunction "DGND_J11") (pintype "passive"))
      (node (ref "U3") (pin "J4") (pinfunction "GND_ANA_PIX_2_J4") (pintype "passive"))
      (node (ref "U3") (pin "J5") (pinfunction "TEST_J5") (pintype "passive"))
      (node (ref "U4") (pin "A11") (pinfunction "DGND_A11") (pintype "passive"))
      (node (ref "U4") (pin "B1") (pinfunction "DGND_B1") (pintype "passive"))
      (node (ref "U4") (pin "C2") (pinfunction "GND_ANA_PIX_0_C2") (pintype "passive"))
      (node (ref "U4") (pin "D4") (pinfunction "DGND_D4") (pintype "passive"))
      (node (ref "U4") (pin "D5") (pinfunction "DGND_D5") (pintype "passive"))
      (node (ref "U4") (pin "D6") (pinfunction "DGND_D6") (pintype "passive"))
      (node (ref "U4") (pin "D7") (pinfunction "DGND_D7") (pintype "passive"))
      (node (ref "U4") (pin "D8") (pinfunction "DGND_D8") (pintype "passive"))
      (node (ref "U4") (pin "E4") (pinfunction "DGND_E4") (pintype "passive"))
      (node (ref "U4") (pin "E5") (pinfunction "DGND_E5") (pintype "passive"))
      (node (ref "U4") (pin "E6") (pinfunction "DGND_E6") (pintype "passive"))
      (node (ref "U4") (pin "E7") (pinfunction "DGND_E7") (pintype "passive"))
      (node (ref "U4") (pin "E8") (pinfunction "DGND_E8") (pintype "passive"))
      (node (ref "U4") (pin "F2") (pinfunction "GND_DIG_ACORE_0_F2") (pintype "passive"))
      (node (ref "U4") (pin "F4") (pinfunction "DGND_F4") (pintype "passive"))
      (node (ref "U4") (pin "F5") (pinfunction "DGND_F5") (pintype "passive"))
      (node (ref "U4") (pin "F6") (pinfunction "DGND_F6") (pintype "passive"))
      (node (ref "U4") (pin "F7") (pinfunction "GND_ANA_ACORE_0_F7") (pintype "passive"))
      (node (ref "U4") (pin "F8") (pinfunction "GND_ANA_ACORE_1_F8") (pintype "passive"))
      (node (ref "U4") (pin "G2") (pinfunction "GND_ANA_PIX_1_G2") (pintype "passive"))
      (node (ref "U4") (pin "H2") (pinfunction "GND_ANA_ACORE_2_H2") (pintype "passive"))
      (node (ref "U4") (pin "H3") (pinfunction "GND_ANA_ACORE_3_H3") (pintype "passive"))
      (node (ref "U4") (pin "H5") (pinfunction "GND_DIG_ACORE_1_H5") (pintype "passive"))
      (node (ref "U4") (pin "J1") (pinfunction "DGND_J1") (pintype "passive"))
      (node (ref "U4") (pin "J11") (pinfunction "DGND_J11") (pintype "passive"))
      (node (ref "U4") (pin "J4") (pinfunction "GND_ANA_PIX_2_J4") (pintype "passive"))
      (node (ref "U4") (pin "J5") (pinfunction "TEST_J5") (pintype "passive"))
    )
    (net (code "53") (name "unconnected-(U1A-ATEST1-PadJ8)") (class "Default")
      (node (ref "U1") (pin "J8") (pinfunction "ATEST1_J8") (pintype "passive"))
    )
    (net (code "54") (name "unconnected-(U1A-ATEST2-PadC1)") (class "Default")
      (node (ref "U1") (pin "C1") (pinfunction "ATEST2_C1") (pintype "passive"))
    )
    (net (code "55") (name "unconnected-(U1A-DATA3N-PadB5)") (class "Default")
      (node (ref "U1") (pin "B5") (pinfunction "DATA3N_B5") (pintype "passive"))
    )
    (net (code "56") (name "unconnected-(U1A-DATA3P-PadA5)") (class "Default")
      (node (ref "U1") (pin "A5") (pinfunction "DATA3P_A5") (pintype "passive"))
    )
    (net (code "57") (name "unconnected-(U1A-DATA4N-PadB4)") (class "Default")
      (node (ref "U1") (pin "B4") (pinfunction "DATA4N_B4") (pintype "passive"))
    )
    (net (code "58") (name "unconnected-(U1A-DATA4P-PadA4)") (class "Default")
      (node (ref "U1") (pin "A4") (pinfunction "DATA4P_A4") (pintype "passive"))
    )
    (net (code "59") (name "unconnected-(U1A-GPI2-PadE1)") (class "Default")
      (node (ref "U1") (pin "E1") (pinfunction "GPI2_E1") (pintype "passive"))
    )
    (net (code "60") (name "unconnected-(U1A-GPI3-PadE2)") (class "Default")
      (node (ref "U1") (pin "E2") (pinfunction "GPI3_E2") (pintype "passive"))
    )
    (net (code "61") (name "unconnected-(U1A-P1_CLKN-PadE10)") (class "Default")
      (node (ref "U1") (pin "E10") (pinfunction "P1_CLKN_E10") (pintype "passive"))
    )
    (net (code "62") (name "unconnected-(U1A-P1_CLKP-PadE11)") (class "Default")
      (node (ref "U1") (pin "E11") (pinfunction "P1_CLKP_E11") (pintype "passive"))
    )
    (net (code "63") (name "unconnected-(U1A-P1_DATA2N-PadD10)") (class "Default")
      (node (ref "U1") (pin "D10") (pinfunction "P1_DATA2N_D10") (pintype "passive"))
    )
    (net (code "64") (name "unconnected-(U1A-P1_DATA2P-PadD11)") (class "Default")
      (node (ref "U1") (pin "D11") (pinfunction "P1_DATA2P_D11") (pintype "passive"))
    )
    (net (code "65") (name "unconnected-(U1A-P1_DATA3N-PadF10)") (class "Default")
      (node (ref "U1") (pin "F10") (pinfunction "P1_DATA3N_F10") (pintype "passive"))
    )
    (net (code "66") (name "unconnected-(U1A-P1_DATA3P-PadF11)") (class "Default")
      (node (ref "U1") (pin "F11") (pinfunction "P1_DATA3P_F11") (pintype "passive"))
    )
    (net (code "67") (name "unconnected-(U1A-P1_DATA4N-PadG10)") (class "Default")
      (node (ref "U1") (pin "G10") (pinfunction "P1_DATA4N_G10") (pintype "passive"))
    )
    (net (code "68") (name "unconnected-(U1A-P1_DATA4P-PadG11)") (class "Default")
      (node (ref "U1") (pin "G11") (pinfunction "P1_DATA4P_G11") (pintype "passive"))
    )
    (net (code "69") (name "unconnected-(U1A-P1_DATAN-PadC10)") (class "Default")
      (node (ref "U1") (pin "C10") (pinfunction "P1_DATAN_C10") (pintype "passive"))
    )
    (net (code "70") (name "unconnected-(U1A-P1_DATAP-PadC11)") (class "Default")
      (node (ref "U1") (pin "C11") (pinfunction "P1_DATAP_C11") (pintype "passive"))
    )
    (net (code "71") (name "unconnected-(U1B-P1_VDD_SLVS_PHY-PadH10)") (class "Default")
      (node (ref "U1") (pin "H10") (pinfunction "P1_VDD_SLVS_PHY_H10") (pintype "passive"))
    )
    (net (code "72") (name "unconnected-(U1B-VDD_SLVS_PHY-PadA3)") (class "Default")
      (node (ref "U1") (pin "A3") (pinfunction "VDD_SLVS_PHY_A3") (pintype "passive"))
    )
    (net (code "73") (name "unconnected-(U2A-ATEST1-PadJ8)") (class "Default")
      (node (ref "U2") (pin "J8") (pinfunction "ATEST1_J8") (pintype "passive"))
    )
    (net (code "74") (name "unconnected-(U2A-ATEST2-PadC1)") (class "Default")
      (node (ref "U2") (pin "C1") (pinfunction "ATEST2_C1") (pintype "passive"))
    )
    (net (code "75") (name "unconnected-(U2A-DATA3N-PadB5)") (class "Default")
      (node (ref "U2") (pin "B5") (pinfunction "DATA3N_B5") (pintype "passive"))
    )
    (net (code "76") (name "unconnected-(U2A-DATA3P-PadA5)") (class "Default")
      (node (ref "U2") (pin "A5") (pinfunction "DATA3P_A5") (pintype "passive"))
    )
    (net (code "77") (name "unconnected-(U2A-DATA4N-PadB4)") (class "Default")
      (node (ref "U2") (pin "B4") (pinfunction "DATA4N_B4") (pintype "passive"))
    )
    (net (code "78") (name "unconnected-(U2A-DATA4P-PadA4)") (class "Default")
      (node (ref "U2") (pin "A4") (pinfunction "DATA4P_A4") (pintype "passive"))
    )
    (net (code "79") (name "unconnected-(U2A-GPI2-PadE1)") (class "Default")
      (node (ref "U2") (pin "E1") (pinfunction "GPI2_E1") (pintype "passive"))
    )
    (net (code "80") (name "unconnected-(U2A-GPI3-PadE2)") (class "Default")
      (node (ref "U2") (pin "E2") (pinfunction "GPI3_E2") (pintype "passive"))
    )
    (net (code "81") (name "unconnected-(U2A-P1_CLKN-PadE10)") (class "Default")
      (node (ref "U2") (pin "E10") (pinfunction "P1_CLKN_E10") (pintype "passive"))
    )
    (net (code "82") (name "unconnected-(U2A-P1_CLKP-PadE11)") (class "Default")
      (node (ref "U2") (pin "E11") (pinfunction "P1_CLKP_E11") (pintype "passive"))
    )
    (net (code "83") (name "unconnected-(U2A-P1_DATA2N-PadD10)") (class "Default")
      (node (ref "U2") (pin "D10") (pinfunction "P1_DATA2N_D10") (pintype "passive"))
    )
    (net (code "84") (name "unconnected-(U2A-P1_DATA2P-PadD11)") (class "Default")
      (node (ref "U2") (pin "D11") (pinfunction "P1_DATA2P_D11") (pintype "passive"))
    )
    (net (code "85") (name "unconnected-(U2A-P1_DATA3N-PadF10)") (class "Default")
      (node (ref "U2") (pin "F10") (pinfunction "P1_DATA3N_F10") (pintype "passive"))
    )
    (net (code "86") (name "unconnected-(U2A-P1_DATA3P-PadF11)") (class "Default")
      (node (ref "U2") (pin "F11") (pinfunction "P1_DATA3P_F11") (pintype "passive"))
    )
    (net (code "87") (name "unconnected-(U2A-P1_DATA4N-PadG10)") (class "Default")
      (node (ref "U2") (pin "G10") (pinfunction "P1_DATA4N_G10") (pintype "passive"))
    )
    (net (code "88") (name "unconnected-(U2A-P1_DATA4P-PadG11)") (class "Default")
      (node (ref "U2") (pin "G11") (pinfunction "P1_DATA4P_G11") (pintype "passive"))
    )
    (net (code "89") (name "unconnected-(U2A-P1_DATAN-PadC10)") (class "Default")
      (node (ref "U2") (pin "C10") (pinfunction "P1_DATAN_C10") (pintype "passive"))
    )
    (net (code "90") (name "unconnected-(U2A-P1_DATAP-PadC11)") (class "Default")
      (node (ref "U2") (pin "C11") (pinfunction "P1_DATAP_C11") (pintype "passive"))
    )
    (net (code "91") (name "unconnected-(U2B-P1_VDD_SLVS_PHY-PadH10)") (class "Default")
      (node (ref "U2") (pin "H10") (pinfunction "P1_VDD_SLVS_PHY_H10") (pintype "passive"))
    )
    (net (code "92") (name "unconnected-(U2B-VDD_SLVS_PHY-PadA3)") (class "Default")
      (node (ref "U2") (pin "A3") (pinfunction "VDD_SLVS_PHY_A3") (pintype "passive"))
    )
    (net (code "93") (name "unconnected-(U3A-ATEST1-PadJ8)") (class "Default")
      (node (ref "U3") (pin "J8") (pinfunction "ATEST1_J8") (pintype "passive"))
    )
    (net (code "94") (name "unconnected-(U3A-ATEST2-PadC1)") (class "Default")
      (node (ref "U3") (pin "C1") (pinfunction "ATEST2_C1") (pintype "passive"))
    )
    (net (code "95") (name "unconnected-(U3A-DATA3N-PadB5)") (class "Default")
      (node (ref "U3") (pin "B5") (pinfunction "DATA3N_B5") (pintype "passive"))
    )
    (net (code "96") (name "unconnected-(U3A-DATA3P-PadA5)") (class "Default")
      (node (ref "U3") (pin "A5") (pinfunction "DATA3P_A5") (pintype "passive"))
    )
    (net (code "97") (name "unconnected-(U3A-DATA4N-PadB4)") (class "Default")
      (node (ref "U3") (pin "B4") (pinfunction "DATA4N_B4") (pintype "passive"))
    )
    (net (code "98") (name "unconnected-(U3A-DATA4P-PadA4)") (class "Default")
      (node (ref "U3") (pin "A4") (pinfunction "DATA4P_A4") (pintype "passive"))
    )
    (net (code "99") (name "unconnected-(U3A-GPI2-PadE1)") (class "Default")
      (node (ref "U3") (pin "E1") (pinfunction "GPI2_E1") (pintype "passive"))
    )
    (net (code "100") (name "unconnected-(U3A-GPI3-PadE2)") (class "Default")
      (node (ref "U3") (pin "E2") (pinfunction "GPI3_E2") (pintype "passive"))
    )
    (net (code "101") (name "unconnected-(U3A-P1_CLKN-PadE10)") (class "Default")
      (node (ref "U3") (pin "E10") (pinfunction "P1_CLKN_E10") (pintype "passive"))
    )
    (net (code "102") (name "unconnected-(U3A-P1_CLKP-PadE11)") (class "Default")
      (node (ref "U3") (pin "E11") (pinfunction "P1_CLKP_E11") (pintype "passive"))
    )
    (net (code "103") (name "unconnected-(U3A-P1_DATA2N-PadD10)") (class "Default")
      (node (ref "U3") (pin "D10") (pinfunction "P1_DATA2N_D10") (pintype "passive"))
    )
    (net (code "104") (name "unconnected-(U3A-P1_DATA2P-PadD11)") (class "Default")
      (node (ref "U3") (pin "D11") (pinfunction "P1_DATA2P_D11") (pintype "passive"))
    )
    (net (code "105") (name "unconnected-(U3A-P1_DATA3N-PadF10)") (class "Default")
      (node (ref "U3") (pin "F10") (pinfunction "P1_DATA3N_F10") (pintype "passive"))
    )
    (net (code "106") (name "unconnected-(U3A-P1_DATA3P-PadF11)") (class "Default")
      (node (ref "U3") (pin "F11") (pinfunction "P1_DATA3P_F11") (pintype "passive"))
    )
    (net (code "107") (name "unconnected-(U3A-P1_DATA4N-PadG10)") (class "Default")
      (node (ref "U3") (pin "G10") (pinfunction "P1_DATA4N_G10") (pintype "passive"))
    )
    (net (code "108") (name "unconnected-(U3A-P1_DATA4P-PadG11)") (class "Default")
      (node (ref "U3") (pin "G11") (pinfunction "P1_DATA4P_G11") (pintype "passive"))
    )
    (net (code "109") (name "unconnected-(U3A-P1_DATAN-PadC10)") (class "Default")
      (node (ref "U3") (pin "C10") (pinfunction "P1_DATAN_C10") (pintype "passive"))
    )
    (net (code "110") (name "unconnected-(U3A-P1_DATAP-PadC11)") (class "Default")
      (node (ref "U3") (pin "C11") (pinfunction "P1_DATAP_C11") (pintype "passive"))
    )
    (net (code "111") (name "unconnected-(U3B-P1_VDD_SLVS_PHY-PadH10)") (class "Default")
      (node (ref "U3") (pin "H10") (pinfunction "P1_VDD_SLVS_PHY_H10") (pintype "passive"))
    )
    (net (code "112") (name "unconnected-(U3B-VDD_SLVS_PHY-PadA3)") (class "Default")
      (node (ref "U3") (pin "A3") (pinfunction "VDD_SLVS_PHY_A3") (pintype "passive"))
    )
    (net (code "113") (name "unconnected-(U4A-ATEST1-PadJ8)") (class "Default")
      (node (ref "U4") (pin "J8") (pinfunction "ATEST1_J8") (pintype "passive"))
    )
    (net (code "114") (name "unconnected-(U4A-ATEST2-PadC1)") (class "Default")
      (node (ref "U4") (pin "C1") (pinfunction "ATEST2_C1") (pintype "passive"))
    )
    (net (code "115") (name "unconnected-(U4A-DATA3N-PadB5)") (class "Default")
      (node (ref "U4") (pin "B5") (pinfunction "DATA3N_B5") (pintype "passive"))
    )
    (net (code "116") (name "unconnected-(U4A-DATA3P-PadA5)") (class "Default")
      (node (ref "U4") (pin "A5") (pinfunction "DATA3P_A5") (pintype "passive"))
    )
    (net (code "117") (name "unconnected-(U4A-DATA4N-PadB4)") (class "Default")
      (node (ref "U4") (pin "B4") (pinfunction "DATA4N_B4") (pintype "passive"))
    )
    (net (code "118") (name "unconnected-(U4A-DATA4P-PadA4)") (class "Default")
      (node (ref "U4") (pin "A4") (pinfunction "DATA4P_A4") (pintype "passive"))
    )
    (net (code "119") (name "unconnected-(U4A-GPI2-PadE1)") (class "Default")
      (node (ref "U4") (pin "E1") (pinfunction "GPI2_E1") (pintype "passive"))
    )
    (net (code "120") (name "unconnected-(U4A-GPI3-PadE2)") (class "Default")
      (node (ref "U4") (pin "E2") (pinfunction "GPI3_E2") (pintype "passive"))
    )
    (net (code "121") (name "unconnected-(U4A-P1_CLKN-PadE10)") (class "Default")
      (node (ref "U4") (pin "E10") (pinfunction "P1_CLKN_E10") (pintype "passive"))
    )
    (net (code "122") (name "unconnected-(U4A-P1_CLKP-PadE11)") (class "Default")
      (node (ref "U4") (pin "E11") (pinfunction "P1_CLKP_E11") (pintype "passive"))
    )
    (net (code "123") (name "unconnected-(U4A-P1_DATA2N-PadD10)") (class "Default")
      (node (ref "U4") (pin "D10") (pinfunction "P1_DATA2N_D10") (pintype "passive"))
    )
    (net (code "124") (name "unconnected-(U4A-P1_DATA2P-PadD11)") (class "Default")
      (node (ref "U4") (pin "D11") (pinfunction "P1_DATA2P_D11") (pintype "passive"))
    )
    (net (code "125") (name "unconnected-(U4A-P1_DATA3N-PadF10)") (class "Default")
      (node (ref "U4") (pin "F10") (pinfunction "P1_DATA3N_F10") (pintype "passive"))
    )
    (net (code "126") (name "unconnected-(U4A-P1_DATA3P-PadF11)") (class "Default")
      (node (ref "U4") (pin "F11") (pinfunction "P1_DATA3P_F11") (pintype "passive"))
    )
    (net (code "127") (name "unconnected-(U4A-P1_DATA4N-PadG10)") (class "Default")
      (node (ref "U4") (pin "G10") (pinfunction "P1_DATA4N_G10") (pintype "passive"))
    )
    (net (code "128") (name "unconnected-(U4A-P1_DATA4P-PadG11)") (class "Default")
      (node (ref "U4") (pin "G11") (pinfunction "P1_DATA4P_G11") (pintype "passive"))
    )
    (net (code "129") (name "unconnected-(U4A-P1_DATAN-PadC10)") (class "Default")
      (node (ref "U4") (pin "C10") (pinfunction "P1_DATAN_C10") (pintype "passive"))
    )
    (net (code "130") (name "unconnected-(U4A-P1_DATAP-PadC11)") (class "Default")
      (node (ref "U4") (pin "C11") (pinfunction "P1_DATAP_C11") (pintype "passive"))
    )
    (net (code "131") (name "unconnected-(U4B-P1_VDD_SLVS_PHY-PadH10)") (class "Default")
      (node (ref "U4") (pin "H10") (pinfunction "P1_VDD_SLVS_PHY_H10") (pintype "passive"))
    )
    (net (code "132") (name "unconnected-(U4B-VDD_SLVS_PHY-PadA3)") (class "Default")
      (node (ref "U4") (pin "A3") (pinfunction "VDD_SLVS_PHY_A3") (pintype "passive"))
    )
  )
)
